# button_connector.net
KiCad netlist of a schematic drawn in EAGLE
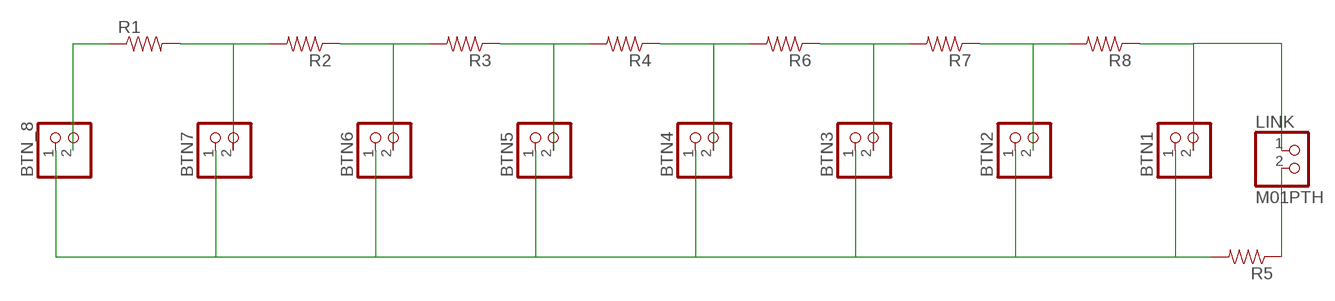
[diagram p0: schematic, sheet 1]

(export (version "E")
  (design (tool "Eeschema 10.0.6"))
  (components
    (comp (ref "BTN1")
      (value "PINHD-1X2")
      (footprint "eagle-import:1X02")
      (libsource (lib "eagle-import") (part "PINHD-1X2"))
    )
    (comp (ref "BTN2")
      (value "PINHD-1X2")
      (footprint "eagle-import:1X02")
      (libsource (lib "eagle-import") (part "PINHD-1X2"))
    )
    (comp (ref "BTN3")
      (value "PINHD-1X2")
      (footprint "eagle-import:1X02")
      (libsource (lib "eagle-import") (part "PINHD-1X2"))
    )
    (comp (ref "BTN4")
      (value "PINHD-1X2")
      (footprint "eagle-import:1X02")
      (libsource (lib "eagle-import") (part "PINHD-1X2"))
    )
    (comp (ref "BTN5")
      (value "PINHD-1X2")
      (footprint "eagle-import:1X02")
      (libsource (lib "eagle-import") (part "PINHD-1X2"))
    )
    (comp (ref "BTN6")
      (value "PINHD-1X2")
      (footprint "eagle-import:1X02")
      (libsource (lib "eagle-import") (part "PINHD-1X2"))
    )
    (comp (ref "BTN7")
      (value "PINHD-1X2")
      (footprint "eagle-import:1X02")
      (libsource (lib "eagle-import") (part "PINHD-1X2"))
    )
    (comp (ref "BTN_8")
      (value "PINHD-1X2")
      (footprint "eagle-import:1X02")
      (libsource (lib "eagle-import") (part "PINHD-1X2"))
    )
    (comp (ref "LINK")
      (value "M01PTH")
      (footprint "eagle-import:1X02")
      (libsource (lib "eagle-import") (part "PINHD-1X2"))
    )
    (comp (ref "R1")
      (value "RESISTORPTH1")
      (footprint "eagle-import:AXIAL-0.3")
      (libsource (lib "eagle-import") (part "RESISTORPTH1"))
    )
    (comp (ref "R2")
      (value "RESISTORPTH1")
      (footprint "eagle-import:AXIAL-0.3")
      (libsource (lib "eagle-import") (part "RESISTORPTH1"))
    )
    (comp (ref "R3")
      (value "RESISTORPTH1")
      (footprint "eagle-import:AXIAL-0.3")
      (libsource (lib "eagle-import") (part "RESISTORPTH1"))
    )
    (comp (ref "R4")
      (value "RESISTORPTH1")
      (footprint "eagle-import:AXIAL-0.3")
      (libsource (lib "eagle-import") (part "RESISTORPTH1"))
    )
    (comp (ref "R5")
      (value "RESISTORPTH1")
      (footprint "eagle-import:AXIAL-0.3")
      (libsource (lib "eagle-import") (part "RESISTORPTH1"))
    )
    (comp (ref "R6")
      (value "RESISTORPTH1")
      (footprint "eagle-import:AXIAL-0.3")
      (libsource (lib "eagle-import") (part "RESISTORPTH1"))
    )
    (comp (ref "R7")
      (value "RESISTORPTH1")
      (footprint "eagle-import:AXIAL-0.3")
      (libsource (lib "eagle-import") (part "RESISTORPTH1"))
    )
    (comp (ref "R8")
      (value "RESISTORPTH1")
      (footprint "eagle-import:AXIAL-0.3")
      (libsource (lib "eagle-import") (part "RESISTORPTH1"))
    )
  )
  (nets
    (net (code "1") (name "Net-(R1-1)") (class "Default")
      (node (ref "BTN_8") (pin "2") (pinfunction "2_2") (pintype "passive"))
      (node (ref "R1") (pin "P$1") (pinfunction "1_P$1") (pintype "passive"))
    )
    (net (code "2") (name "Net-(R1-2)") (class "Default")
      (node (ref "BTN7") (pin "2") (pinfunction "2_2") (pintype "passive"))
      (node (ref "R1") (pin "P$2") (pinfunction "2_P$2") (pintype "passive"))
      (node (ref "R2") (pin "P$2") (pinfunction "2_P$2") (pintype "passive"))
    )
    (net (code "3") (name "Net-(R2-1)") (class "Default")
      (node (ref "BTN6") (pin "2") (pinfunction "2_2") (pintype "passive"))
      (node (ref "R2") (pin "P$1") (pinfunction "1_P$1") (pintype "passive"))
      (node (ref "R3") (pin "P$2") (pinfunction "2_P$2") (pintype "passive"))
    )
    (net (code "4") (name "Net-(R3-1)") (class "Default")
      (node (ref "BTN5") (pin "2") (pinfunction "2_2") (pintype "passive"))
      (node (ref "R3") (pin "P$1") (pinfunction "1_P$1") (pintype "passive"))
      (node (ref "R4") (pin "P$2") (pinfunction "2_P$2") (pintype "passive"))
    )
    (net (code "5") (name "Net-(R4-1)") (class "Default")
      (node (ref "BTN4") (pin "2") (pinfunction "2_2") (pintype "passive"))
      (node (ref "R4") (pin "P$1") (pinfunction "1_P$1") (pintype "passive"))
      (node (ref "R6") (pin "P$2") (pinfunction "2_P$2") (pintype "passive"))
    )
    (net (code "6") (name "Net-(R5-1)") (class "Default")
      (node (ref "LINK") (pin "2") (pinfunction "2_2") (pintype "passive"))
      (node (ref "R5") (pin "P$1") (pinfunction "1_P$1") (pintype "passive"))
    )
    (net (code "7") (name "Net-(R5-2)") (class "Default")
      (node (ref "BTN1") (pin "1") (pinfunction "1_1") (pintype "passive"))
      (node (ref "BTN2") (pin "1") (pinfunction "1_1") (pintype "passive"))
      (node (ref "BTN3") (pin "1") (pinfunction "1_1") (pintype "passive"))
      (node (ref "BTN4") (pin "1") (pinfunction "1_1") (pintype "passive"))
      (node (ref "BTN5") (pin "1") (pinfunction "1_1") (pintype "passive"))
      (node (ref "BTN6") (pin "1") (pinfunction "1_1") (pintype "passive"))
      (node (ref "BTN7") (pin "1") (pinfunction "1_1") (pintype "passive"))
      (node (ref "BTN_8") (pin "1") (pinfunction "1_1") (pintype "passive"))
      (node (ref "R5") (pin "P$2") (pinfunction "2_P$2") (pintype "passive"))
    )
    (net (code "8") (name "Net-(R6-1)") (class "Default")
      (node (ref "BTN3") (pin "2") (pinfunction "2_2") (pintype "passive"))
      (node (ref "R6") (pin "P$1") (pinfunction "1_P$1") (pintype "passive"))
      (node (ref "R7") (pin "P$2") (pinfunction "2_P$2") (pintype "passive"))
    )
    (net (code "9") (name "Net-(R7-1)") (class "Default")
      (node (ref "BTN2") (pin "2") (pinfunction "2_2") (pintype "passive"))
      (node (ref "R7") (pin "P$1") (pinfunction "1_P$1") (pintype "passive"))
      (node (ref "R8") (pin "P$2") (pinfunction "2_P$2") (pintype "passive"))
    )
    (net (code "10") (name "Net-(R8-1)") (class "Default")
      (node (ref "BTN1") (pin "2") (pinfunction "2_2") (pintype "passive"))
      (node (ref "LINK") (pin "1") (pinfunction "1_1") (pintype "passive"))
      (node (ref "R8") (pin "P$1") (pinfunction "1_P$1") (pintype "passive"))
    )
  )
)
